# kapacz_drecyciel.net
KiCad netlist of a schematic drawn in EAGLE
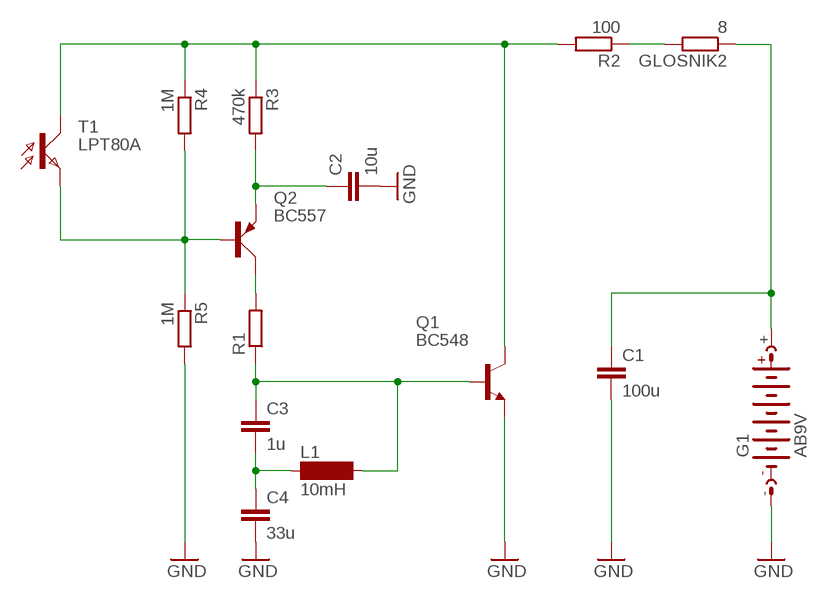
[diagram p0: schematic, sheet 1]

(export (version "E")
  (design (tool "Eeschema 10.0.6"))
  (components
    (comp (ref "C1")
      (value "100u")
      (footprint "eagle-import:C2.5-3")
      (libsource (lib "eagle-import") (part "C2,5-3"))
    )
    (comp (ref "C2")
      (value "10u")
      (footprint "eagle-import:C2.5-3")
      (libsource (lib "eagle-import") (part "C2,5-3"))
    )
    (comp (ref "C3")
      (value "1u")
      (footprint "eagle-import:C2.5-3")
      (libsource (lib "eagle-import") (part "C2,5-3"))
    )
    (comp (ref "C4")
      (value "33u")
      (footprint "eagle-import:C2.5-3")
      (libsource (lib "eagle-import") (part "C2,5-3"))
    )
    (comp (ref "G1")
      (value "AB9V")
      (footprint "eagle-import:AB9V")
      (libsource (lib "eagle-import") (part "AB9V"))
    )
    (comp (ref "GLOSNIK2")
      (value "8")
      (footprint "eagle-import:M0805")
      (libsource (lib "eagle-import") (part "resistor_R-EU_M0805"))
    )
    (comp (ref "L1")
      (value "10mH")
      (footprint "eagle-import:BS11")
      (libsource (lib "eagle-import") (part "BS11"))
    )
    (comp (ref "Q1")
      (value "BC548")
      (footprint "eagle-import:TO92-EBC")
      (libsource (lib "eagle-import") (part "BC548"))
    )
    (comp (ref "Q2")
      (value "BC557")
      (footprint "eagle-import:SOT54A")
      (libsource (lib "eagle-import") (part "BC557"))
    )
    (comp (ref "R1")
      (value "R-EU_0204/7")
      (footprint "eagle-import:0204_7")
      (libsource (lib "eagle-import") (part "R-EU_0204/7"))
    )
    (comp (ref "R2")
      (value "100")
      (footprint "eagle-import:M0805")
      (libsource (lib "eagle-import") (part "resistor_R-EU_M0805"))
    )
    (comp (ref "R3")
      (value "470k")
      (footprint "eagle-import:M0805")
      (libsource (lib "eagle-import") (part "resistor_R-EU_M0805"))
    )
    (comp (ref "R4")
      (value "1M")
      (footprint "eagle-import:M0805")
      (libsource (lib "eagle-import") (part "resistor_R-EU_M0805"))
    )
    (comp (ref "R5")
      (value "1M")
      (footprint "eagle-import:M0805")
      (libsource (lib "eagle-import") (part "resistor_R-EU_M0805"))
    )
    (comp (ref "T1")
      (value "LPT80A")
      (footprint "eagle-import:LPT80A")
      (libsource (lib "eagle-import") (part "LPT80A"))
    )
  )
  (nets
    (net (code "1") (name "GND") (class "Default")
      (node (ref "C1") (pin "2") (pinfunction "2_2") (pintype "passive"))
      (node (ref "C2") (pin "2") (pinfunction "2_2") (pintype "passive"))
      (node (ref "C4") (pin "2") (pinfunction "2_2") (pintype "passive"))
      (node (ref "G1") (pin "-") (pinfunction "-_-") (pintype "passive"))
      (node (ref "Q1") (pin "E") (pinfunction "E_E") (pintype "passive"))
      (node (ref "R5") (pin "2") (pinfunction "2_2") (pintype "passive"))
    )
    (net (code "2") (name "Net-(C1-Pad1)") (class "Default")
      (node (ref "C1") (pin "1") (pinfunction "1_1") (pintype "passive"))
      (node (ref "G1") (pin "+") (pinfunction "+_+") (pintype "passive"))
      (node (ref "GLOSNIK2") (pin "1") (pinfunction "1_1") (pintype "passive"))
    )
    (net (code "3") (name "Net-(C2-Pad1)") (class "Default")
      (node (ref "C2") (pin "1") (pinfunction "1_1") (pintype "passive"))
      (node (ref "Q2") (pin "E") (pinfunction "E_E") (pintype "passive"))
      (node (ref "R3") (pin "2") (pinfunction "2_2") (pintype "passive"))
    )
    (net (code "4") (name "Net-(C3-Pad1)") (class "Default")
      (node (ref "C3") (pin "1") (pinfunction "1_1") (pintype "passive"))
      (node (ref "L1") (pin "2") (pinfunction "2_2") (pintype "passive"))
      (node (ref "Q1") (pin "B") (pinfunction "B_B") (pintype "passive"))
      (node (ref "R1") (pin "1") (pinfunction "1_1") (pintype "passive"))
    )
    (net (code "5") (name "Net-(C3-Pad2)") (class "Default")
      (node (ref "C3") (pin "2") (pinfunction "2_2") (pintype "passive"))
      (node (ref "C4") (pin "1") (pinfunction "1_1") (pintype "passive"))
      (node (ref "L1") (pin "1") (pinfunction "1_1") (pintype "passive"))
    )
    (net (code "6") (name "Net-(GLOSNIK2-Pad2)") (class "Default")
      (node (ref "GLOSNIK2") (pin "2") (pinfunction "2_2") (pintype "passive"))
      (node (ref "R2") (pin "1") (pinfunction "1_1") (pintype "passive"))
    )
    (net (code "7") (name "Net-(Q1-PadC)") (class "Default")
      (node (ref "Q1") (pin "C") (pinfunction "C_C") (pintype "passive"))
      (node (ref "R2") (pin "2") (pinfunction "2_2") (pintype "passive"))
      (node (ref "R3") (pin "1") (pinfunction "1_1") (pintype "passive"))
      (node (ref "R4") (pin "1") (pinfunction "1_1") (pintype "passive"))
      (node (ref "T1") (pin "C") (pinfunction "C_C") (pintype "passive"))
    )
    (net (code "8") (name "Net-(Q2-PadB)") (class "Default")
      (node (ref "Q2") (pin "B") (pinfunction "B_B") (pintype "passive"))
      (node (ref "R4") (pin "2") (pinfunction "2_2") (pintype "passive"))
      (node (ref "R5") (pin "1") (pinfunction "1_1") (pintype "passive"))
      (node (ref "T1") (pin "E") (pinfunction "E_E") (pintype "passive"))
    )
    (net (code "9") (name "Net-(Q2-PadC)") (class "Default")
      (node (ref "Q2") (pin "C") (pinfunction "C_C") (pintype "passive"))
      (node (ref "R1") (pin "2") (pinfunction "2_2") (pintype "passive"))
    )
  )
)
